# Receptor_U.net
KiCad netlist of a schematic drawn in Altium Designer
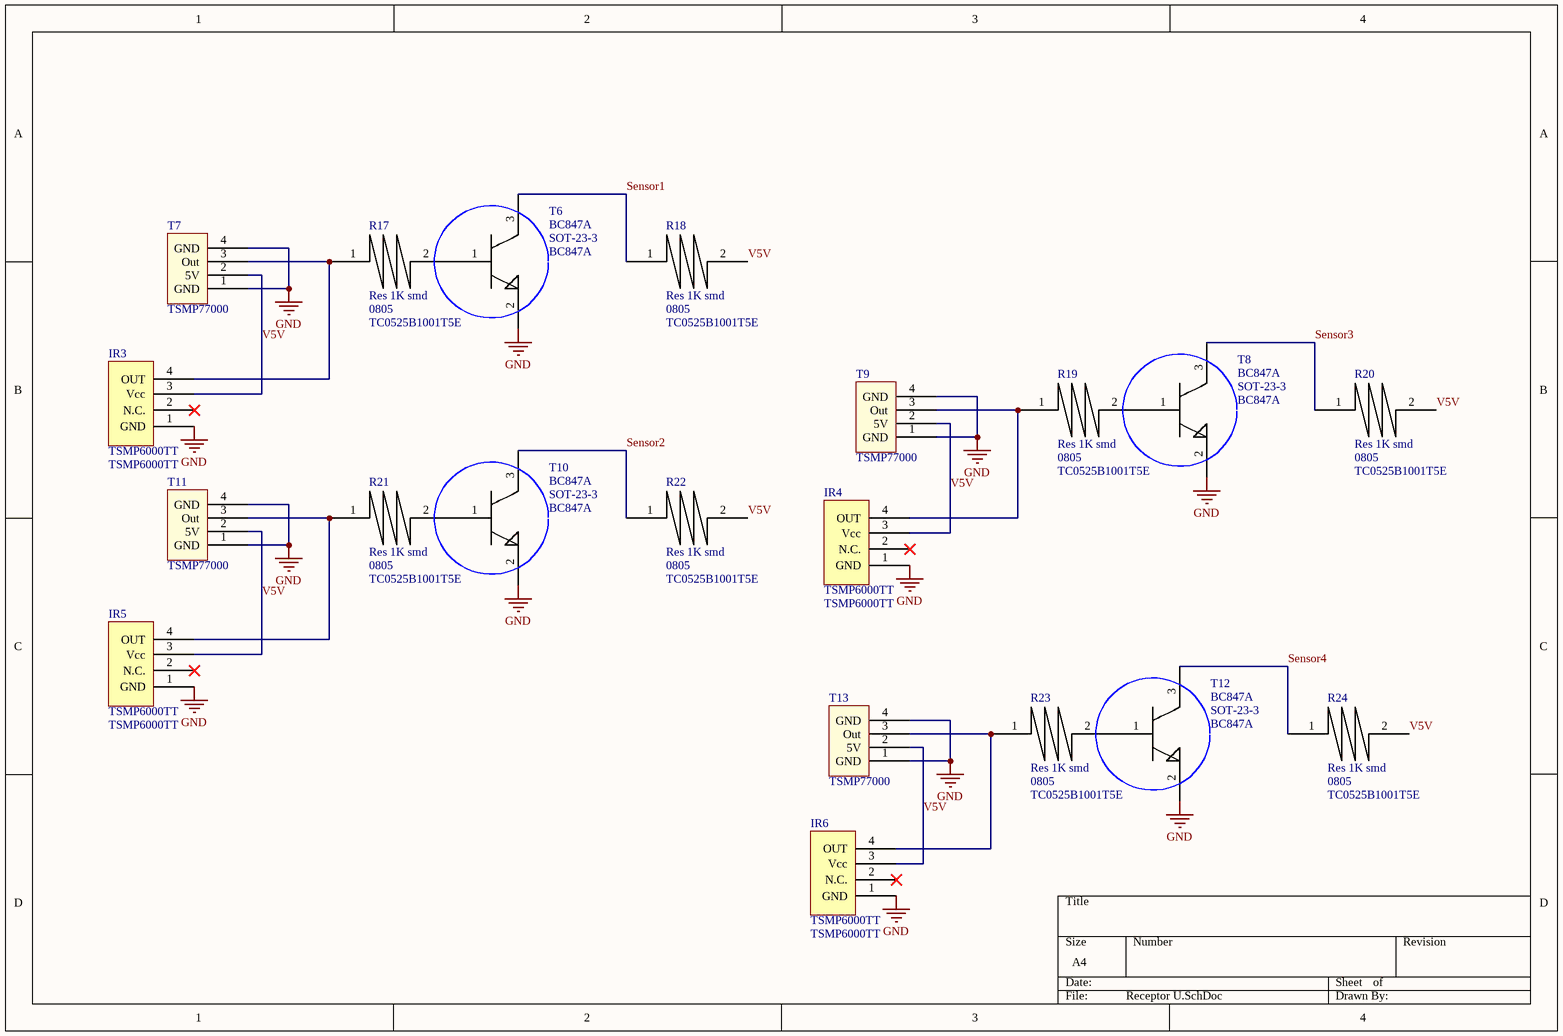
[diagram p0: Receptor U.SchDoc]

(export (version "E")
  (design (tool "Eeschema 10.0.6"))
  (components
    (comp (ref "IR3")
      (value "TSMP6000TT")
      (footprint "TSMP6000TT")
      (fields (field (name "PART") "TSMP6000TT"))
      (libsource (lib "Integrated_Library") (part "TSMP6000TT"))
    )
    (comp (ref "IR4")
      (value "TSMP6000TT")
      (footprint "TSMP6000TT")
      (fields (field (name "PART") "TSMP6000TT"))
      (libsource (lib "Integrated_Library") (part "TSMP6000TT"))
    )
    (comp (ref "IR5")
      (value "TSMP6000TT")
      (footprint "TSMP6000TT")
      (fields (field (name "PART") "TSMP6000TT"))
      (libsource (lib "Integrated_Library") (part "TSMP6000TT"))
    )
    (comp (ref "IR6")
      (value "TSMP6000TT")
      (footprint "TSMP6000TT")
      (fields (field (name "PART") "TSMP6000TT"))
      (libsource (lib "Integrated_Library") (part "TSMP6000TT"))
    )
    (comp (ref "R17")
      (value "Res 1K smd")
      (footprint "RES 1K")
      (fields (field (name "PACKAGE") "0805") (field (name "MFR.PART #") "TC0525B1001T5E"))
      (libsource (lib "Integrated_Library") (part "Res 1K smd"))
    )
    (comp (ref "R18")
      (value "Res 1K smd")
      (footprint "RES 1K")
      (fields (field (name "PACKAGE") "0805") (field (name "MFR.PART #") "TC0525B1001T5E"))
      (libsource (lib "Integrated_Library") (part "Res 1K smd"))
    )
    (comp (ref "R19")
      (value "Res 1K smd")
      (footprint "RES 1K")
      (fields (field (name "PACKAGE") "0805") (field (name "MFR.PART #") "TC0525B1001T5E"))
      (libsource (lib "Integrated_Library") (part "Res 1K smd"))
    )
    (comp (ref "R20")
      (value "Res 1K smd")
      (footprint "RES 1K")
      (fields (field (name "PACKAGE") "0805") (field (name "MFR.PART #") "TC0525B1001T5E"))
      (libsource (lib "Integrated_Library") (part "Res 1K smd"))
    )
    (comp (ref "R21")
      (value "Res 1K smd")
      (footprint "RES 1K")
      (fields (field (name "PACKAGE") "0805") (field (name "MFR.PART #") "TC0525B1001T5E"))
      (libsource (lib "Integrated_Library") (part "Res 1K smd"))
    )
    (comp (ref "R22")
      (value "Res 1K smd")
      (footprint "RES 1K")
      (fields (field (name "PACKAGE") "0805") (field (name "MFR.PART #") "TC0525B1001T5E"))
      (libsource (lib "Integrated_Library") (part "Res 1K smd"))
    )
    (comp (ref "R23")
      (value "Res 1K smd")
      (footprint "RES 1K")
      (fields (field (name "PACKAGE") "0805") (field (name "MFR.PART #") "TC0525B1001T5E"))
      (libsource (lib "Integrated_Library") (part "Res 1K smd"))
    )
    (comp (ref "R24")
      (value "Res 1K smd")
      (footprint "RES 1K")
      (fields (field (name "PACKAGE") "0805") (field (name "MFR.PART #") "TC0525B1001T5E"))
      (libsource (lib "Integrated_Library") (part "Res 1K smd"))
    )
    (comp (ref "T6")
      (value "BC847A")
      (footprint "BC847A")
      (fields (field (name "PACKAGE") "SOT-23-3") (field (name "MFR.PART #") "BC847A"))
      (libsource (lib "Integrated_Library") (part "BC847A"))
    )
    (comp (ref "T7")
      (value "TSMP77000")
      (footprint "TSMP77000")
      (libsource (lib "Integrated_Library") (part "TSMP77000"))
    )
    (comp (ref "T8")
      (value "BC847A")
      (footprint "BC847A")
      (fields (field (name "PACKAGE") "SOT-23-3") (field (name "MFR.PART #") "BC847A"))
      (libsource (lib "Integrated_Library") (part "BC847A"))
    )
    (comp (ref "T9")
      (value "TSMP77000")
      (footprint "TSMP77000")
      (libsource (lib "Integrated_Library") (part "TSMP77000"))
    )
    (comp (ref "T10")
      (value "BC847A")
      (footprint "BC847A")
      (fields (field (name "PACKAGE") "SOT-23-3") (field (name "MFR.PART #") "BC847A"))
      (libsource (lib "Integrated_Library") (part "BC847A"))
    )
    (comp (ref "T11")
      (value "TSMP77000")
      (footprint "TSMP77000")
      (libsource (lib "Integrated_Library") (part "TSMP77000"))
    )
    (comp (ref "T12")
      (value "BC847A")
      (footprint "BC847A")
      (fields (field (name "PACKAGE") "SOT-23-3") (field (name "MFR.PART #") "BC847A"))
      (libsource (lib "Integrated_Library") (part "BC847A"))
    )
    (comp (ref "T13")
      (value "TSMP77000")
      (footprint "TSMP77000")
      (libsource (lib "Integrated_Library") (part "TSMP77000"))
    )
  )
  (nets
    (net (code "1") (name "/Sensor1") (class "Default")
      (node (ref "R18") (pin "1") (pinfunction "1_1") (pintype "passive"))
      (node (ref "T6") (pin "3") (pinfunction "3_3") (pintype "passive"))
    )
    (net (code "2") (name "/Sensor2") (class "Default")
      (node (ref "R22") (pin "1") (pinfunction "1_1") (pintype "passive"))
      (node (ref "T10") (pin "3") (pinfunction "3_3") (pintype "passive"))
    )
    (net (code "3") (name "/Sensor3") (class "Default")
      (node (ref "R20") (pin "1") (pinfunction "1_1") (pintype "passive"))
      (node (ref "T8") (pin "3") (pinfunction "3_3") (pintype "passive"))
    )
    (net (code "4") (name "/Sensor4") (class "Default")
      (node (ref "R24") (pin "1") (pinfunction "1_1") (pintype "passive"))
      (node (ref "T12") (pin "3") (pinfunction "3_3") (pintype "passive"))
    )
    (net (code "5") (name "/V5V") (class "Default")
      (node (ref "IR3") (pin "3") (pinfunction "Vcc_3") (pintype "passive"))
      (node (ref "IR4") (pin "3") (pinfunction "Vcc_3") (pintype "passive"))
      (node (ref "IR5") (pin "3") (pinfunction "Vcc_3") (pintype "passive"))
      (node (ref "IR6") (pin "3") (pinfunction "Vcc_3") (pintype "passive"))
      (node (ref "R18") (pin "2") (pinfunction "2_2") (pintype "passive"))
      (node (ref "R20") (pin "2") (pinfunction "2_2") (pintype "passive"))
      (node (ref "R22") (pin "2") (pinfunction "2_2") (pintype "passive"))
      (node (ref "R24") (pin "2") (pinfunction "2_2") (pintype "passive"))
      (node (ref "T11") (pin "2") (pinfunction "5V_2") (pintype "passive"))
      (node (ref "T13") (pin "2") (pinfunction "5V_2") (pintype "passive"))
      (node (ref "T7") (pin "2") (pinfunction "5V_2") (pintype "passive"))
      (node (ref "T9") (pin "2") (pinfunction "5V_2") (pintype "passive"))
    )
    (net (code "6") (name "GND") (class "Default")
      (node (ref "IR3") (pin "1") (pinfunction "GND_1") (pintype "passive"))
      (node (ref "IR4") (pin "1") (pinfunction "GND_1") (pintype "passive"))
      (node (ref "IR5") (pin "1") (pinfunction "GND_1") (pintype "passive"))
      (node (ref "IR6") (pin "1") (pinfunction "GND_1") (pintype "passive"))
      (node (ref "T10") (pin "2") (pinfunction "2_2") (pintype "passive"))
      (node (ref "T11") (pin "1") (pinfunction "GND_1") (pintype "passive"))
      (node (ref "T11") (pin "4") (pinfunction "GND_4") (pintype "passive"))
      (node (ref "T12") (pin "2") (pinfunction "2_2") (pintype "passive"))
      (node (ref "T13") (pin "1") (pinfunction "GND_1") (pintype "passive"))
      (node (ref "T13") (pin "4") (pinfunction "GND_4") (pintype "passive"))
      (node (ref "T6") (pin "2") (pinfunction "2_2") (pintype "passive"))
      (node (ref "T7") (pin "1") (pinfunction "GND_1") (pintype "passive"))
      (node (ref "T7") (pin "4") (pinfunction "GND_4") (pintype "passive"))
      (node (ref "T8") (pin "2") (pinfunction "2_2") (pintype "passive"))
      (node (ref "T9") (pin "1") (pinfunction "GND_1") (pintype "passive"))
      (node (ref "T9") (pin "4") (pinfunction "GND_4") (pintype "passive"))
    )
    (net (code "7") (name "Net-(IR3-OUT)") (class "Default")
      (node (ref "IR3") (pin "4") (pinfunction "OUT_4") (pintype "passive"))
      (node (ref "R17") (pin "1") (pinfunction "1_1") (pintype "passive"))
      (node (ref "T7") (pin "3") (pinfunction "Out_3") (pintype "passive"))
    )
    (net (code "8") (name "Net-(IR4-OUT)") (class "Default")
      (node (ref "IR4") (pin "4") (pinfunction "OUT_4") (pintype "passive"))
      (node (ref "R19") (pin "1") (pinfunction "1_1") (pintype "passive"))
      (node (ref "T9") (pin "3") (pinfunction "Out_3") (pintype "passive"))
    )
    (net (code "9") (name "Net-(IR5-OUT)") (class "Default")
      (node (ref "IR5") (pin "4") (pinfunction "OUT_4") (pintype "passive"))
      (node (ref "R21") (pin "1") (pinfunction "1_1") (pintype "passive"))
      (node (ref "T11") (pin "3") (pinfunction "Out_3") (pintype "passive"))
    )
    (net (code "10") (name "Net-(IR6-OUT)") (class "Default")
      (node (ref "IR6") (pin "4") (pinfunction "OUT_4") (pintype "passive"))
      (node (ref "R23") (pin "1") (pinfunction "1_1") (pintype "passive"))
      (node (ref "T13") (pin "3") (pinfunction "Out_3") (pintype "passive"))
    )
    (net (code "11") (name "Net-(R17-Pad2)") (class "Default")
      (node (ref "R17") (pin "2") (pinfunction "2_2") (pintype "passive"))
      (node (ref "T6") (pin "1") (pinfunction "1_1") (pintype "passive"))
    )
    (net (code "12") (name "Net-(R19-Pad2)") (class "Default")
      (node (ref "R19") (pin "2") (pinfunction "2_2") (pintype "passive"))
      (node (ref "T8") (pin "1") (pinfunction "1_1") (pintype "passive"))
    )
    (net (code "13") (name "Net-(R21-Pad2)") (class "Default")
      (node (ref "R21") (pin "2") (pinfunction "2_2") (pintype "passive"))
      (node (ref "T10") (pin "1") (pinfunction "1_1") (pintype "passive"))
    )
    (net (code "14") (name "Net-(R23-Pad2)") (class "Default")
      (node (ref "R23") (pin "2") (pinfunction "2_2") (pintype "passive"))
      (node (ref "T12") (pin "1") (pinfunction "1_1") (pintype "passive"))
    )
    (net (code "15") (name "unconnected-(IR3-N.C.-Pad2)") (class "Default")
      (node (ref "IR3") (pin "2") (pinfunction "N.C._2") (pintype "passive+no_connect"))
    )
    (net (code "16") (name "unconnected-(IR4-N.C.-Pad2)") (class "Default")
      (node (ref "IR4") (pin "2") (pinfunction "N.C._2") (pintype "passive+no_connect"))
    )
    (net (code "17") (name "unconnected-(IR5-N.C.-Pad2)") (class "Default")
      (node (ref "IR5") (pin "2") (pinfunction "N.C._2") (pintype "passive+no_connect"))
    )
    (net (code "18") (name "unconnected-(IR6-N.C.-Pad2)") (class "Default")
      (node (ref "IR6") (pin "2") (pinfunction "N.C._2") (pintype "passive+no_connect"))
    )
  )
)
